# STM32_MCU.net
KiCad netlist of a schematic drawn in Altium Designer
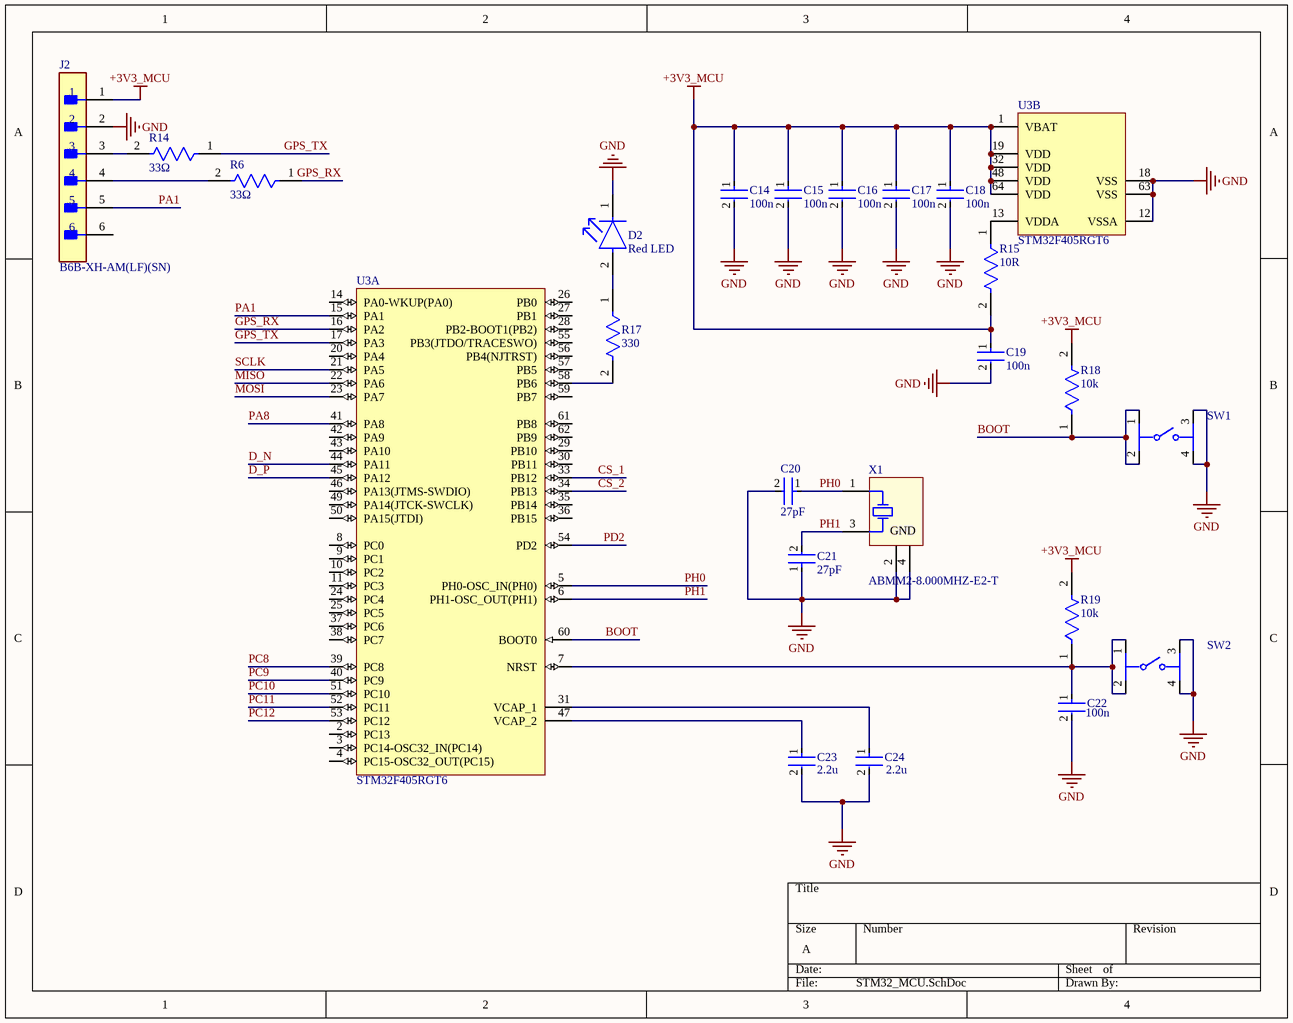
[diagram p0: STM32_MCU.SchDoc]

(export (version "E")
  (design (tool "Eeschema 10.0.6"))
  (components
    (comp (ref "C14")
      (value "0603B104K250CT")
      (footprint "FP-0603B104K250CT-IPC_C")
      (description "CAP CER 0.1UF 25V X7R 0603")
      (fields (field (name "TOLERANCE") "10%") (field (name "CAPACITANCE") "100n"))
      (libsource (lib "Altium Content Vault") (part "b4654b650e69147ec39a6b967a45e02"))
    )
    (comp (ref "C15")
      (value "0603B104K250CT")
      (footprint "FP-0603B104K250CT-IPC_C")
      (description "CAP CER 0.1UF 25V X7R 0603")
      (fields (field (name "TOLERANCE") "10%") (field (name "CAPACITANCE") "100n"))
      (libsource (lib "Altium Content Vault") (part "b4654b650e69147ec39a6b967a45e02"))
    )
    (comp (ref "C16")
      (value "0603B104K250CT")
      (footprint "FP-0603B104K250CT-IPC_C")
      (description "CAP CER 0.1UF 25V X7R 0603")
      (fields (field (name "TOLERANCE") "10%") (field (name "CAPACITANCE") "100n"))
      (libsource (lib "Altium Content Vault") (part "b4654b650e69147ec39a6b967a45e02"))
    )
    (comp (ref "C17")
      (value "0603B104K250CT")
      (footprint "FP-0603B104K250CT-IPC_C")
      (description "CAP CER 0.1UF 25V X7R 0603")
      (fields (field (name "TOLERANCE") "10%") (field (name "CAPACITANCE") "100n"))
      (libsource (lib "Altium Content Vault") (part "b4654b650e69147ec39a6b967a45e02"))
    )
    (comp (ref "C18")
      (value "0603B104K250CT")
      (footprint "FP-0603B104K250CT-IPC_C")
      (description "CAP CER 0.1UF 25V X7R 0603")
      (fields (field (name "TOLERANCE") "10%") (field (name "CAPACITANCE") "100n"))
      (libsource (lib "Altium Content Vault") (part "b4654b650e69147ec39a6b967a45e02"))
    )
    (comp (ref "C19")
      (value "0603B104K250CT")
      (footprint "FP-0603B104K250CT-IPC_C")
      (description "CAP CER 0.1UF 25V X7R 0603")
      (fields (field (name "TOLERANCE") "10%") (field (name "CAPACITANCE") "100n"))
      (libsource (lib "Altium Content Vault") (part "b4654b650e69147ec39a6b967a45e02"))
    )
    (comp (ref "C20")
      (value "CL05C270JB5NNNC")
      (footprint "FP-CL934-IPC_C")
      (description "Cap Ceramic 27pF 50V C0G ±5% SMD 0402 +125°C Paper T/R")
      (fields
        (field (name "TOLERANCE") "5%")
        (field (name "CAPACITANCE") "27pF")
        (field (name "VOLTAGE") "50V")
      )
      (libsource (lib "Altium Content Vault") (part "b4654b650e69147ec39a6b967a45e02"))
    )
    (comp (ref "C21")
      (value "CL05C270JB5NNNC")
      (footprint "FP-CL934-IPC_C")
      (description "Cap Ceramic 27pF 50V C0G ±5% SMD 0402 +125°C Paper T/R")
      (fields
        (field (name "TOLERANCE") "5%")
        (field (name "CAPACITANCE") "27pF")
        (field (name "VOLTAGE") "50V")
      )
      (libsource (lib "Altium Content Vault") (part "b4654b650e69147ec39a6b967a45e02"))
    )
    (comp (ref "C22")
      (value "0603B104K250CT")
      (footprint "FP-0603B104K250CT-IPC_C")
      (description "CAP CER 0.1UF 25V X7R 0603")
      (fields (field (name "TOLERANCE") "10%") (field (name "CAPACITANCE") "100n"))
      (libsource (lib "Altium Content Vault") (part "b4654b650e69147ec39a6b967a45e02"))
    )
    (comp (ref "C23")
      (value "CL10A225KO8NNNC")
      (footprint "FP-CL10-IPC_A")
      (description "Cap Ceramic 2.2uF 16V X5R ±10% Pad SMD 0603 +85°C T/R")
      (fields
        (field (name "CAPACITANCE") "2.2u")
        (field (name "TOLERANCE") "10%")
        (field (name "VOLTAGE") "16V")
      )
      (libsource (lib "Altium Content Vault") (part "b4654b650e69147ec39a6b967a45e02"))
    )
    (comp (ref "C24")
      (value "CL10A225KO8NNNC")
      (footprint "FP-CL10-IPC_A")
      (description "Cap Ceramic 2.2uF 16V X5R ±10% Pad SMD 0603 +85°C T/R")
      (fields
        (field (name "CAPACITANCE") "2.2u")
        (field (name "TOLERANCE") "10%")
        (field (name "VOLTAGE") "16V")
      )
      (libsource (lib "Altium Content Vault") (part "b4654b650e69147ec39a6b967a45e02"))
    )
    (comp (ref "D2")
      (value "Red LED")
      (footprint "FP-LTST-S270KRKT-MFG")
      (description "LED RED CLEAR CHIP SMD R/A\r\n\r\nLTST-S270KRKT")
      (libsource (lib "Altium Content Vault") (part "8706943c75ba83719d021d2fdc84c58"))
    )
    (comp (ref "J2")
      (value "B6B-XH-AM(LF)(SN)")
      (footprint "FP-B6B-XH-AM_LF_SN-MFG")
      (description "CONN HEADER VERT 6POS 2.5MM")
      (libsource (lib "Altium Content Vault") (part "f2cb566baf1c37ab5a3b8e90bbeafd6"))
    )
    (comp (ref "R6")
      (value "33Ω")
      (footprint "FP-SR0603-MFG")
      (description "RES 33 OHM 1% 1/4W 0603")
      (fields
        (field (name "MANUFACTURER") "Yageo")
        (field (name "MANUFACTURER PART NUMBER") "SR0603FR-7T33RL")
      )
      (libsource (lib "Altium Content Vault") (part "1029c3af85768c4190bb7ad29bc67b5"))
    )
    (comp (ref "R14")
      (value "33Ω")
      (footprint "FP-SR0603-MFG")
      (description "RES 33 OHM 1% 1/4W 0603")
      (fields
        (field (name "MANUFACTURER") "Yageo")
        (field (name "MANUFACTURER PART NUMBER") "SR0603FR-7T33RL")
      )
      (libsource (lib "Altium Content Vault") (part "1029c3af85768c4190bb7ad29bc67b5"))
    )
    (comp (ref "R15")
      (value "AF0603JR-0710RL")
      (footprint "FP-AF0603-IPC_C")
      (description "Anti-Sulfurated Chip Resistors Automotive Grade 10Ω 5% 200ppm/°C 0603")
      (fields (field (name "TOLERANCE") "5%") (field (name "RESISTANCE") "10R"))
      (libsource (lib "Altium Content Vault") (part "1029c3af85768c4190bb7ad29bc67b5"))
    )
    (comp (ref "R17")
      (value "RT0603FRD07330RL")
      (footprint "FP-RT0603-MFG")
      (description "RES SMD 330 OHM 1% 1/10W 0603")
      (fields
        (field (name "RESISTANCE") "330")
        (field (name "TOLERANCE") "0.01")
        (field (name "OCTOPART") "https://octopart.com/rt0603frd07330rl-yageo-71395358")
      )
      (libsource (lib "Altium Content Vault") (part "1029c3af85768c4190bb7ad29bc67b5"))
    )
    (comp (ref "R18")
      (value "10k")
      (footprint "FP-AC0603-IPC_A")
      (description "RES 10kΩ 5.00% 0.2W 0603")
      (fields (field (name "Comment") "AC0603JR-7W10KL"))
      (libsource (lib "Altium Content Vault") (part "1029c3af85768c4190bb7ad29bc67b5"))
    )
    (comp (ref "R19")
      (value "10k")
      (footprint "FP-AC0603-IPC_A")
      (description "RES 10kΩ 5.00% 0.2W 0603")
      (fields (field (name "Comment") "AC0603JR-7W10KL"))
      (libsource (lib "Altium Content Vault") (part "1029c3af85768c4190bb7ad29bc67b5"))
    )
    (comp (ref "SW1")
      (value "PTS526SK15SMTR2LFS")
      (footprint "FP-PTS526SK15SMTR2LFS-MFG")
      (description "TACT 5.2 X 5.2, 1.5 MM H, 260GF,")
      (fields
        (field (name "MANUFACTURER") "C&K")
        (field (name "OCTOPART") "https://octopart.com/pts526+sk15+smtr2+lfs-c%26k+components-100617999")
      )
      (libsource (lib "Altium Content Vault") (part "b8895f3f4cefb76e1819d2863dba89b"))
    )
    (comp (ref "SW2")
      (value "PTS526SK15SMTR2LFS")
      (footprint "FP-PTS526SK15SMTR2LFS-MFG")
      (description "TACT 5.2 X 5.2, 1.5 MM H, 260GF,")
      (fields
        (field (name "MANUFACTURER") "C&K")
        (field (name "OCTOPART") "https://octopart.com/pts526+sk15+smtr2+lfs-c%26k+components-100617999")
      )
      (libsource (lib "Altium Content Vault") (part "b8895f3f4cefb76e1819d2863dba89b"))
    )
    (comp (ref "U3")
      (value "STM32F405RGT6")
      (footprint "STM-LQFP64_M")
      (fields (field (name "MANUFACTURER") "STMicroelectronics"))
      (libsource (lib "Altium Content Vault") (part "MC-ARM-STM32F4X5-SQ64"))
    )
    (comp (ref "X1")
      (value "ABMM2-8.000MHZ-E2-T")
      (footprint "ABRA-ABMM2-4_V")
      (fields (field (name "MANUFACTURER") "Abracon"))
      (libsource (lib "Altium Content Vault") (part "ABRA-XTAL_1-3-4"))
    )
  )
  (nets
    (net (code "1") (name "+3V3_MCU") (class "Default")
      (node (ref "C14") (pin "1") (pinfunction "1_1") (pintype "passive"))
      (node (ref "C15") (pin "1") (pinfunction "1_1") (pintype "passive"))
      (node (ref "C16") (pin "1") (pinfunction "1_1") (pintype "passive"))
      (node (ref "C17") (pin "1") (pinfunction "1_1") (pintype "passive"))
      (node (ref "C18") (pin "1") (pinfunction "1_1") (pintype "passive"))
      (node (ref "C19") (pin "1") (pinfunction "1_1") (pintype "passive"))
      (node (ref "J2") (pin "1") (pinfunction "1_1") (pintype "passive"))
      (node (ref "R15") (pin "2") (pinfunction "2_2") (pintype "passive"))
      (node (ref "R18") (pin "2") (pinfunction "2_2") (pintype "passive"))
      (node (ref "R19") (pin "2") (pinfunction "2_2") (pintype "passive"))
      (node (ref "U3") (pin "1") (pinfunction "VBAT_1") (pintype "power_in"))
      (node (ref "U3") (pin "19") (pinfunction "VDD_19") (pintype "power_in"))
      (node (ref "U3") (pin "32") (pinfunction "VDD_32") (pintype "power_in"))
      (node (ref "U3") (pin "48") (pinfunction "VDD_48") (pintype "power_in"))
      (node (ref "U3") (pin "64") (pinfunction "VDD_64") (pintype "power_in"))
    )
    (net (code "2") (name "/BOOT") (class "Default")
      (node (ref "R18") (pin "1") (pinfunction "1_1") (pintype "passive"))
      (node (ref "SW1") (pin "1") (pinfunction "1_1") (pintype "passive"))
      (node (ref "SW1") (pin "2") (pinfunction "2_2") (pintype "passive"))
      (node (ref "U3") (pin "60") (pinfunction "BOOT0_60") (pintype "input"))
    )
    (net (code "3") (name "/CS_1") (class "Default")
      (node (ref "U3") (pin "33") (pinfunction "PB12_33") (pintype "bidirectional"))
    )
    (net (code "4") (name "/CS_2") (class "Default")
      (node (ref "U3") (pin "34") (pinfunction "PB13_34") (pintype "bidirectional"))
    )
    (net (code "5") (name "/D_N") (class "Default")
      (node (ref "U3") (pin "44") (pinfunction "PA11_44") (pintype "bidirectional"))
    )
    (net (code "6") (name "/D_P") (class "Default")
      (node (ref "U3") (pin "45") (pinfunction "PA12_45") (pintype "bidirectional"))
    )
    (net (code "7") (name "/GPS_RX") (class "Default")
      (node (ref "R6") (pin "1") (pinfunction "1_1") (pintype "passive"))
      (node (ref "U3") (pin "16") (pinfunction "PA2_16") (pintype "bidirectional"))
    )
    (net (code "8") (name "/GPS_TX") (class "Default")
      (node (ref "R14") (pin "1") (pinfunction "1_1") (pintype "passive"))
      (node (ref "U3") (pin "17") (pinfunction "PA3_17") (pintype "bidirectional"))
    )
    (net (code "9") (name "/MISO") (class "Default")
      (node (ref "U3") (pin "22") (pinfunction "PA6_22") (pintype "bidirectional"))
    )
    (net (code "10") (name "/MOSI") (class "Default")
      (node (ref "U3") (pin "23") (pinfunction "PA7_23") (pintype "bidirectional"))
    )
    (net (code "11") (name "/PA1") (class "Default")
      (node (ref "J2") (pin "5") (pinfunction "5_5") (pintype "passive"))
      (node (ref "U3") (pin "15") (pinfunction "PA1_15") (pintype "bidirectional"))
    )
    (net (code "12") (name "/PA8") (class "Default")
      (node (ref "U3") (pin "41") (pinfunction "PA8_41") (pintype "bidirectional"))
    )
    (net (code "13") (name "/PC8") (class "Default")
      (node (ref "U3") (pin "39") (pinfunction "PC8_39") (pintype "bidirectional"))
    )
    (net (code "14") (name "/PC9") (class "Default")
      (node (ref "U3") (pin "40") (pinfunction "PC9_40") (pintype "bidirectional"))
    )
    (net (code "15") (name "/PC10") (class "Default")
      (node (ref "U3") (pin "51") (pinfunction "PC10_51") (pintype "bidirectional"))
    )
    (net (code "16") (name "/PC11") (class "Default")
      (node (ref "U3") (pin "52") (pinfunction "PC11_52") (pintype "bidirectional"))
    )
    (net (code "17") (name "/PC12") (class "Default")
      (node (ref "U3") (pin "53") (pinfunction "PC12_53") (pintype "bidirectional"))
    )
    (net (code "18") (name "/PD2") (class "Default")
      (node (ref "U3") (pin "54") (pinfunction "PD2_54") (pintype "bidirectional"))
    )
    (net (code "19") (name "/PH0") (class "Default")
      (node (ref "C20") (pin "1") (pinfunction "1_1") (pintype "passive"))
      (node (ref "U3") (pin "5") (pinfunction "PH0-OSC_IN(PH0)_5") (pintype "bidirectional"))
      (node (ref "X1") (pin "1") (pinfunction "X1_1") (pintype "passive"))
    )
    (net (code "20") (name "/PH1") (class "Default")
      (node (ref "C21") (pin "2") (pinfunction "2_2") (pintype "passive"))
      (node (ref "U3") (pin "6") (pinfunction "PH1-OSC_OUT(PH1)_6") (pintype "bidirectional"))
      (node (ref "X1") (pin "3") (pinfunction "X2_3") (pintype "passive"))
    )
    (net (code "21") (name "/SCLK") (class "Default")
      (node (ref "U3") (pin "21") (pinfunction "PA5_21") (pintype "bidirectional"))
    )
    (net (code "22") (name "GND") (class "Default")
      (node (ref "C14") (pin "2") (pinfunction "2_2") (pintype "passive"))
      (node (ref "C15") (pin "2") (pinfunction "2_2") (pintype "passive"))
      (node (ref "C16") (pin "2") (pinfunction "2_2") (pintype "passive"))
      (node (ref "C17") (pin "2") (pinfunction "2_2") (pintype "passive"))
      (node (ref "C18") (pin "2") (pinfunction "2_2") (pintype "passive"))
      (node (ref "C19") (pin "2") (pinfunction "2_2") (pintype "passive"))
      (node (ref "C20") (pin "2") (pinfunction "2_2") (pintype "passive"))
      (node (ref "C21") (pin "1") (pinfunction "1_1") (pintype "passive"))
      (node (ref "C22") (pin "2") (pinfunction "2_2") (pintype "passive"))
      (node (ref "C23") (pin "2") (pinfunction "2_2") (pintype "passive"))
      (node (ref "C24") (pin "2") (pinfunction "2_2") (pintype "passive"))
      (node (ref "D2") (pin "1") (pinfunction "C_1") (pintype "passive"))
      (node (ref "J2") (pin "2") (pinfunction "2_2") (pintype "passive"))
      (node (ref "SW1") (pin "3") (pinfunction "3_3") (pintype "passive"))
      (node (ref "SW1") (pin "4") (pinfunction "4_4") (pintype "passive"))
      (node (ref "SW2") (pin "3") (pinfunction "3_3") (pintype "passive"))
      (node (ref "SW2") (pin "4") (pinfunction "4_4") (pintype "passive"))
      (node (ref "U3") (pin "12") (pinfunction "VSSA_12") (pintype "power_in"))
      (node (ref "U3") (pin "18") (pinfunction "VSS_18") (pintype "power_in"))
      (node (ref "U3") (pin "63") (pinfunction "VSS_63") (pintype "power_in"))
      (node (ref "X1") (pin "2") (pinfunction "GND_2") (pintype "power_in"))
      (node (ref "X1") (pin "4") (pinfunction "GND_4") (pintype "power_in"))
    )
    (net (code "23") (name "Net-(D2-A)") (class "Default")
      (node (ref "D2") (pin "2") (pinfunction "A_2") (pintype "passive"))
      (node (ref "R17") (pin "1") (pinfunction "1_1") (pintype "passive"))
    )
    (net (code "24") (name "Net-(J2-Pad3)") (class "Default")
      (node (ref "J2") (pin "3") (pinfunction "3_3") (pintype "passive"))
      (node (ref "R14") (pin "2") (pinfunction "2_2") (pintype "passive"))
    )
    (net (code "25") (name "Net-(J2-Pad4)") (class "Default")
      (node (ref "J2") (pin "4") (pinfunction "4_4") (pintype "passive"))
      (node (ref "R6") (pin "2") (pinfunction "2_2") (pintype "passive"))
    )
    (net (code "26") (name "Net-(U3A-NRST)") (class "Default")
      (node (ref "C22") (pin "1") (pinfunction "1_1") (pintype "passive"))
      (node (ref "R19") (pin "1") (pinfunction "1_1") (pintype "passive"))
      (node (ref "SW2") (pin "1") (pinfunction "1_1") (pintype "passive"))
      (node (ref "SW2") (pin "2") (pinfunction "2_2") (pintype "passive"))
      (node (ref "U3") (pin "7") (pinfunction "NRST_7") (pintype "bidirectional"))
    )
    (net (code "27") (name "Net-(U3A-PB6)") (class "Default")
      (node (ref "R17") (pin "2") (pinfunction "2_2") (pintype "passive"))
      (node (ref "U3") (pin "58") (pinfunction "PB6_58") (pintype "bidirectional"))
    )
    (net (code "28") (name "Net-(U3A-VCAP_1)") (class "Default")
      (node (ref "C24") (pin "1") (pinfunction "1_1") (pintype "passive"))
      (node (ref "U3") (pin "31") (pinfunction "VCAP_1_31") (pintype "power_in"))
    )
    (net (code "29") (name "Net-(U3A-VCAP_2)") (class "Default")
      (node (ref "C23") (pin "1") (pinfunction "1_1") (pintype "passive"))
      (node (ref "U3") (pin "47") (pinfunction "VCAP_2_47") (pintype "power_in"))
    )
    (net (code "30") (name "Net-(U3B-VDDA)") (class "Default")
      (node (ref "R15") (pin "1") (pinfunction "1_1") (pintype "passive"))
      (node (ref "U3") (pin "13") (pinfunction "VDDA_13") (pintype "power_in"))
    )
    (net (code "31") (name "unconnected-(J2-Pad6)") (class "Default")
      (node (ref "J2") (pin "6") (pinfunction "6_6") (pintype "passive"))
    )
    (net (code "32") (name "unconnected-(U3A-PA0-WKUP(PA0)-Pad14)") (class "Default")
      (node (ref "U3") (pin "14") (pinfunction "PA0-WKUP(PA0)_14") (pintype "bidirectional"))
    )
    (net (code "33") (name "unconnected-(U3A-PA4-Pad20)") (class "Default")
      (node (ref "U3") (pin "20") (pinfunction "PA4_20") (pintype "bidirectional"))
    )
    (net (code "34") (name "unconnected-(U3A-PA9-Pad42)") (class "Default")
      (node (ref "U3") (pin "42") (pinfunction "PA9_42") (pintype "bidirectional"))
    )
    (net (code "35") (name "unconnected-(U3A-PA10-Pad43)") (class "Default")
      (node (ref "U3") (pin "43") (pinfunction "PA10_43") (pintype "bidirectional"))
    )
    (net (code "36") (name "unconnected-(U3A-PA13(JTMS-SWDIO)-Pad46)") (class "Default")
      (node (ref "U3") (pin "46") (pinfunction "PA13(JTMS-SWDIO)_46") (pintype "bidirectional"))
    )
    (net (code "37") (name "unconnected-(U3A-PA14(JTCK-SWCLK)-Pad49)") (class "Default")
      (node (ref "U3") (pin "49") (pinfunction "PA14(JTCK-SWCLK)_49") (pintype "bidirectional"))
    )
    (net (code "38") (name "unconnected-(U3A-PA15(JTDI)-Pad50)") (class "Default")
      (node (ref "U3") (pin "50") (pinfunction "PA15(JTDI)_50") (pintype "bidirectional"))
    )
    (net (code "39") (name "unconnected-(U3A-PB0-Pad26)") (class "Default")
      (node (ref "U3") (pin "26") (pinfunction "PB0_26") (pintype "bidirectional"))
    )
    (net (code "40") (name "unconnected-(U3A-PB1-Pad27)") (class "Default")
      (node (ref "U3") (pin "27") (pinfunction "PB1_27") (pintype "bidirectional"))
    )
    (net (code "41") (name "unconnected-(U3A-PB2-BOOT1(PB2)-Pad28)") (class "Default")
      (node (ref "U3") (pin "28") (pinfunction "PB2-BOOT1(PB2)_28") (pintype "bidirectional"))
    )
    (net (code "42") (name "unconnected-(U3A-PB3(JTDO{slash}TRACESWO)-Pad55)") (class "Default")
      (node (ref "U3") (pin "55") (pinfunction "PB3(JTDO/TRACESWO)_55") (pintype "bidirectional"))
    )
    (net (code "43") (name "unconnected-(U3A-PB4(NJTRST)-Pad56)") (class "Default")
      (node (ref "U3") (pin "56") (pinfunction "PB4(NJTRST)_56") (pintype "bidirectional"))
    )
    (net (code "44") (name "unconnected-(U3A-PB5-Pad57)") (class "Default")
      (node (ref "U3") (pin "57") (pinfunction "PB5_57") (pintype "bidirectional"))
    )
    (net (code "45") (name "unconnected-(U3A-PB7-Pad59)") (class "Default")
      (node (ref "U3") (pin "59") (pinfunction "PB7_59") (pintype "bidirectional"))
    )
    (net (code "46") (name "unconnected-(U3A-PB8-Pad61)") (class "Default")
      (node (ref "U3") (pin "61") (pinfunction "PB8_61") (pintype "bidirectional"))
    )
    (net (code "47") (name "unconnected-(U3A-PB9-Pad62)") (class "Default")
      (node (ref "U3") (pin "62") (pinfunction "PB9_62") (pintype "bidirectional"))
    )
    (net (code "48") (name "unconnected-(U3A-PB10-Pad29)") (class "Default")
      (node (ref "U3") (pin "29") (pinfunction "PB10_29") (pintype "bidirectional"))
    )
    (net (code "49") (name "unconnected-(U3A-PB11-Pad30)") (class "Default")
      (node (ref "U3") (pin "30") (pinfunction "PB11_30") (pintype "bidirectional"))
    )
    (net (code "50") (name "unconnected-(U3A-PB14-Pad35)") (class "Default")
      (node (ref "U3") (pin "35") (pinfunction "PB14_35") (pintype "bidirectional"))
    )
    (net (code "51") (name "unconnected-(U3A-PB15-Pad36)") (class "Default")
      (node (ref "U3") (pin "36") (pinfunction "PB15_36") (pintype "bidirectional"))
    )
    (net (code "52") (name "unconnected-(U3A-PC0-Pad8)") (class "Default")
      (node (ref "U3") (pin "8") (pinfunction "PC0_8") (pintype "bidirectional"))
    )
    (net (code "53") (name "unconnected-(U3A-PC1-Pad9)") (class "Default")
      (node (ref "U3") (pin "9") (pinfunction "PC1_9") (pintype "bidirectional"))
    )
    (net (code "54") (name "unconnected-(U3A-PC2-Pad10)") (class "Default")
      (node (ref "U3") (pin "10") (pinfunction "PC2_10") (pintype "bidirectional"))
    )
    (net (code "55") (name "unconnected-(U3A-PC3-Pad11)") (class "Default")
      (node (ref "U3") (pin "11") (pinfunction "PC3_11") (pintype "bidirectional"))
    )
    (net (code "56") (name "unconnected-(U3A-PC4-Pad24)") (class "Default")
      (node (ref "U3") (pin "24") (pinfunction "PC4_24") (pintype "bidirectional"))
    )
    (net (code "57") (name "unconnected-(U3A-PC5-Pad25)") (class "Default")
      (node (ref "U3") (pin "25") (pinfunction "PC5_25") (pintype "bidirectional"))
    )
    (net (code "58") (name "unconnected-(U3A-PC6-Pad37)") (class "Default")
      (node (ref "U3") (pin "37") (pinfunction "PC6_37") (pintype "bidirectional"))
    )
    (net (code "59") (name "unconnected-(U3A-PC7-Pad38)") (class "Default")
      (node (ref "U3") (pin "38") (pinfunction "PC7_38") (pintype "bidirectional"))
    )
    (net (code "60") (name "unconnected-(U3A-PC13-Pad2)") (class "Default")
      (node (ref "U3") (pin "2") (pinfunction "PC13_2") (pintype "bidirectional"))
    )
    (net (code "61") (name "unconnected-(U3A-PC14-OSC32_IN(PC14)-Pad3)") (class "Default")
      (node (ref "U3") (pin "3") (pinfunction "PC14-OSC32_IN(PC14)_3") (pintype "bidirectional"))
    )
    (net (code "62") (name "unconnected-(U3A-PC15-OSC32_OUT(PC15)-Pad4)") (class "Default")
      (node (ref "U3") (pin "4") (pinfunction "PC15-OSC32_OUT(PC15)_4") (pintype "bidirectional"))
    )
  )
)
